# transmisorPCB_2_2.net
KiCad netlist of a schematic drawn in EAGLE
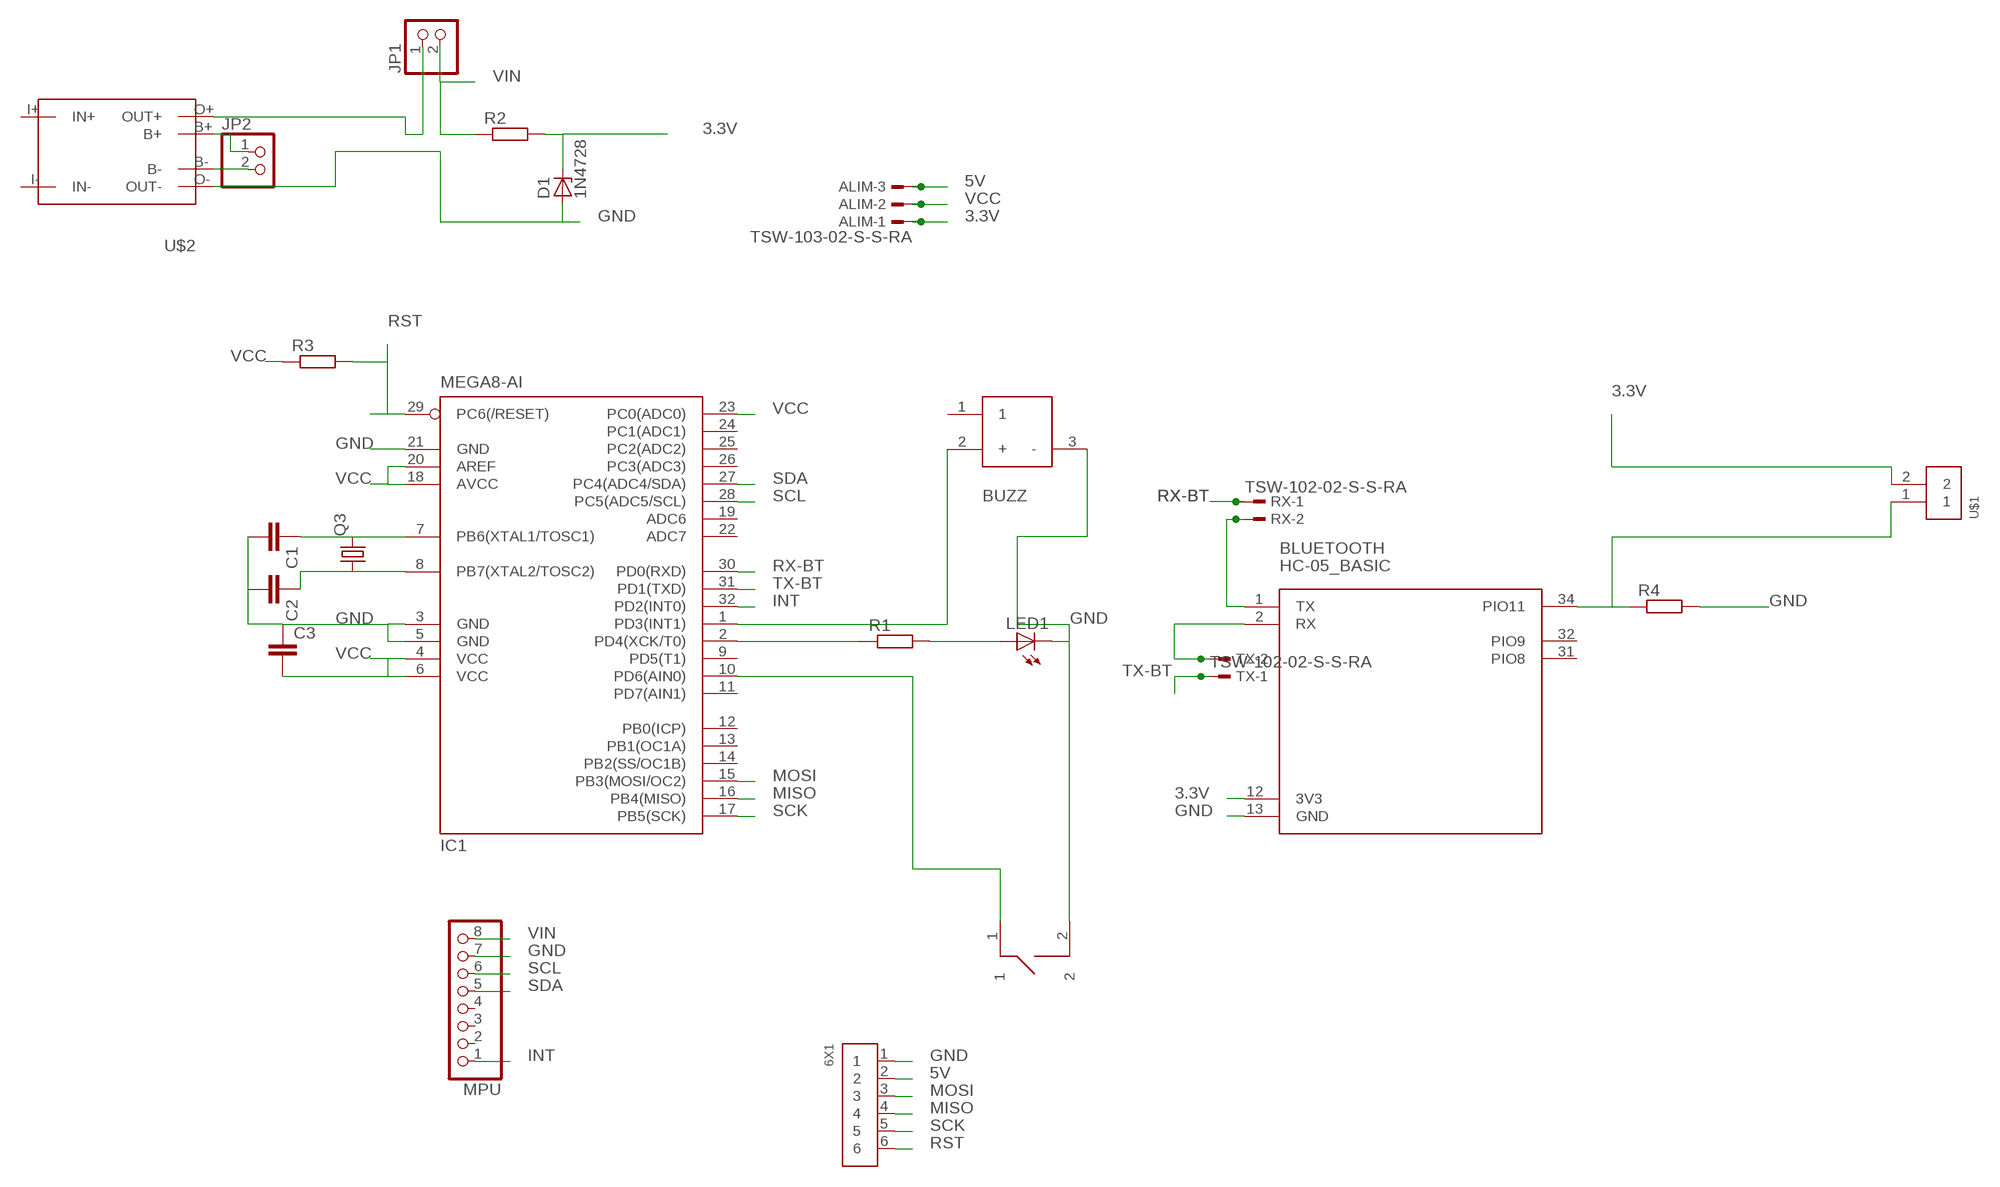
[diagram p0: schematic, sheet 1]

(export (version "E")
  (design (tool "Eeschema 10.0.6"))
  (components
    (comp (ref "6X1")
      (value "PINHEAD_1X6")
      (footprint "eagle-import:PINHEAD_125_1X6")
      (libsource (lib "eagle-import") (part "PINHEAD_1X6"))
    )
    (comp (ref "ALIM")
      (value "TSW-103-02-S-S-RA")
      (footprint "eagle-import:TSW-103-02-S-S-RA")
      (libsource (lib "eagle-import") (part "TSW-103-02-S-S-RA"))
    )
    (comp (ref "BLUETOOTH")
      (value "HC-05_BASIC")
      (footprint "eagle-import:BLUETOOTH_SMD")
      (libsource (lib "eagle-import") (part "HC-05_BASIC"))
    )
    (comp (ref "BUZZ")
      (value "SM05ET02A")
      (footprint "eagle-import:SM05ET02A")
      (libsource (lib "eagle-import") (part "SM05ET02A"))
    )
    (comp (ref "C1")
      (value "C-EUC0402K")
      (footprint "eagle-import:C0402K")
      (libsource (lib "eagle-import") (part "C-EUC0402K"))
    )
    (comp (ref "C2")
      (value "C-EUC0402K")
      (footprint "eagle-import:C0402K")
      (libsource (lib "eagle-import") (part "C-EUC0402K"))
    )
    (comp (ref "C3")
      (value "C-EUC0402K")
      (footprint "eagle-import:C0402K")
      (libsource (lib "eagle-import") (part "C-EUC0402K"))
    )
    (comp (ref "D1")
      (value "1N4728")
      (footprint "eagle-import:DO41Z10")
      (libsource (lib "eagle-import") (part "1N4728"))
    )
    (comp (ref "IC1")
      (value "MEGA8-AI")
      (footprint "eagle-import:TQFP32-08")
      (fields (field (name "MPN") "ATMEGA8-16AU"))
      (libsource (lib "eagle-import") (part "MEGA8-AI"))
    )
    (comp (ref "JP1")
      (value "PINHD-1X2")
      (footprint "eagle-import:1X02")
      (libsource (lib "eagle-import") (part "PINHD-1X2"))
    )
    (comp (ref "JP2")
      (value "PINHD-1X2")
      (footprint "eagle-import:1X02")
      (libsource (lib "eagle-import") (part "PINHD-1X2"))
    )
    (comp (ref "LED1")
      (value "LEDCHIPLED-0603-TTW")
      (footprint "eagle-import:CHIPLED-0603-TTW")
      (libsource (lib "eagle-import") (part "LEDCHIPLED-0603-TTW"))
    )
    (comp (ref "MPU")
      (value "PINHD-1X8")
      (footprint "eagle-import:1X08")
      (libsource (lib "eagle-import") (part "PINHD-1X8"))
    )
    (comp (ref "PUSH")
      (value "PUSH_SMD")
      (footprint "eagle-import:PUSH_SMD")
      (libsource (lib "eagle-import") (part "PUSH_SMD"))
    )
    (comp (ref "Q3")
      (value "CRYSTALHC49U70")
      (footprint "eagle-import:HC49U70")
      (libsource (lib "eagle-import") (part "CRYSTALHC49U70"))
    )
    (comp (ref "R1")
      (value "R-EU_M1206")
      (footprint "eagle-import:M1206")
      (libsource (lib "eagle-import") (part "R-EU_M1206"))
    )
    (comp (ref "R2")
      (value "R-EU_R2512")
      (footprint "eagle-import:R2512")
      (libsource (lib "eagle-import") (part "resistor_R-EU_R2512"))
    )
    (comp (ref "R3")
      (value "R-EU_M1206")
      (footprint "eagle-import:M1206")
      (libsource (lib "eagle-import") (part "R-EU_M1206"))
    )
    (comp (ref "R4")
      (value "R-EU_M1206")
      (footprint "eagle-import:M1206")
      (libsource (lib "eagle-import") (part "R-EU_M1206"))
    )
    (comp (ref "RX")
      (value "TSW-102-02-S-S-RA")
      (footprint "eagle-import:TSW-102-02-S-S-RA")
      (libsource (lib "eagle-import") (part "TSW-102-02-S-S-RA"))
    )
    (comp (ref "TX")
      (value "TSW-102-02-S-S-RA")
      (footprint "eagle-import:TSW-102-02-S-S-RA")
      (libsource (lib "eagle-import") (part "TSW-102-02-S-S-RA"))
    )
    (comp (ref "U$1")
      (value "CP150_1X2")
      (footprint "eagle-import:CP150_1X2")
      (libsource (lib "eagle-import") (part "CP150_1X2"))
    )
    (comp (ref "U$2")
      (value "TP4056")
      (footprint "eagle-import:TP4056")
      (libsource (lib "eagle-import") (part "TP4056"))
    )
  )
  (nets
    (net (code "1") (name "/3.3V") (class "Default")
      (node (ref "ALIM") (pin "1") (pinfunction "1_1") (pintype "passive"))
      (node (ref "BLUETOOTH") (pin "12") (pinfunction "3V3_12") (pintype "bidirectional"))
      (node (ref "D1") (pin "C") (pinfunction "C_C") (pintype "passive"))
      (node (ref "R2") (pin "2") (pinfunction "2_2") (pintype "passive"))
      (node (ref "U$1") (pin "2") (pinfunction "2_2") (pintype "bidirectional"))
    )
    (net (code "2") (name "/5V") (class "Default")
      (node (ref "6X1") (pin "2") (pinfunction "2_2") (pintype "bidirectional"))
      (node (ref "ALIM") (pin "3") (pinfunction "1_3") (pintype "passive"))
    )
    (net (code "3") (name "/GND") (class "Default")
      (node (ref "6X1") (pin "1") (pinfunction "1_1") (pintype "bidirectional"))
      (node (ref "BLUETOOTH") (pin "13") (pinfunction "GND_13") (pintype "bidirectional"))
      (node (ref "BUZZ") (pin "3") (pinfunction "-_3") (pintype "bidirectional"))
      (node (ref "C1") (pin "2") (pinfunction "2_2") (pintype "passive"))
      (node (ref "C2") (pin "2") (pinfunction "2_2") (pintype "passive"))
      (node (ref "C3") (pin "1") (pinfunction "1_1") (pintype "passive"))
      (node (ref "D1") (pin "A") (pinfunction "A_A") (pintype "passive"))
      (node (ref "IC1") (pin "21") (pinfunction "GND_21") (pintype "power_in"))
      (node (ref "IC1") (pin "3") (pinfunction "GND_3") (pintype "power_in"))
      (node (ref "IC1") (pin "5") (pinfunction "GND_5") (pintype "power_in"))
      (node (ref "LED1") (pin "C@1") (pinfunction "C_C@1") (pintype "passive"))
      (node (ref "MPU") (pin "7") (pinfunction "7_7") (pintype "passive"))
      (node (ref "PUSH") (pin "2") (pinfunction "2_2") (pintype "bidirectional"))
      (node (ref "R4") (pin "2") (pinfunction "2_2") (pintype "passive"))
      (node (ref "U$2") (pin "O-") (pinfunction "OUT-_O-") (pintype "bidirectional"))
    )
    (net (code "4") (name "/INT") (class "Default")
      (node (ref "IC1") (pin "32") (pinfunction "PD2(INT0)_32") (pintype "bidirectional"))
      (node (ref "MPU") (pin "1") (pinfunction "1_1") (pintype "passive"))
    )
    (net (code "5") (name "/MISO") (class "Default")
      (node (ref "6X1") (pin "4") (pinfunction "4_4") (pintype "bidirectional"))
      (node (ref "IC1") (pin "16") (pinfunction "PB4(MISO)_16") (pintype "bidirectional"))
    )
    (net (code "6") (name "/MOSI") (class "Default")
      (node (ref "6X1") (pin "3") (pinfunction "3_3") (pintype "bidirectional"))
      (node (ref "IC1") (pin "15") (pinfunction "PB3(MOSI/OC2)_15") (pintype "bidirectional"))
    )
    (net (code "7") (name "/RST") (class "Default")
      (node (ref "6X1") (pin "6") (pinfunction "6_6") (pintype "bidirectional"))
      (node (ref "IC1") (pin "29") (pinfunction "PC6(/RESET)_29") (pintype "bidirectional"))
      (node (ref "R3") (pin "2") (pinfunction "2_2") (pintype "passive"))
    )
    (net (code "8") (name "/RX-BT") (class "Default")
      (node (ref "IC1") (pin "30") (pinfunction "PD0(RXD)_30") (pintype "bidirectional"))
      (node (ref "RX") (pin "1") (pinfunction "1_1") (pintype "passive"))
    )
    (net (code "9") (name "/SCK") (class "Default")
      (node (ref "6X1") (pin "5") (pinfunction "5_5") (pintype "bidirectional"))
      (node (ref "IC1") (pin "17") (pinfunction "PB5(SCK)_17") (pintype "bidirectional"))
    )
    (net (code "10") (name "/SCL") (class "Default")
      (node (ref "IC1") (pin "28") (pinfunction "PC5(ADC5/SCL)_28") (pintype "bidirectional"))
      (node (ref "MPU") (pin "6") (pinfunction "6_6") (pintype "passive"))
    )
    (net (code "11") (name "/SDA") (class "Default")
      (node (ref "IC1") (pin "27") (pinfunction "PC4(ADC4/SDA)_27") (pintype "bidirectional"))
      (node (ref "MPU") (pin "5") (pinfunction "5_5") (pintype "passive"))
    )
    (net (code "12") (name "/TX-BT") (class "Default")
      (node (ref "IC1") (pin "31") (pinfunction "PD1(TXD)_31") (pintype "bidirectional"))
      (node (ref "TX") (pin "1") (pinfunction "1_1") (pintype "passive"))
    )
    (net (code "13") (name "/VCC") (class "Default")
      (node (ref "ALIM") (pin "2") (pinfunction "1_2") (pintype "passive"))
      (node (ref "C3") (pin "2") (pinfunction "2_2") (pintype "passive"))
      (node (ref "IC1") (pin "18") (pinfunction "AVCC_18") (pintype "power_in"))
      (node (ref "IC1") (pin "20") (pinfunction "AREF_20") (pintype "passive"))
      (node (ref "IC1") (pin "23") (pinfunction "PC0(ADC0)_23") (pintype "bidirectional"))
      (node (ref "IC1") (pin "4") (pinfunction "VCC_4") (pintype "power_in"))
      (node (ref "IC1") (pin "6") (pinfunction "VCC_6") (pintype "power_in"))
      (node (ref "R3") (pin "1") (pinfunction "1_1") (pintype "passive"))
    )
    (net (code "14") (name "/VIN") (class "Default")
      (node (ref "JP1") (pin "2") (pinfunction "2_2") (pintype "passive"))
      (node (ref "MPU") (pin "8") (pinfunction "8_8") (pintype "passive"))
      (node (ref "R2") (pin "1") (pinfunction "1_1") (pintype "passive"))
    )
    (net (code "15") (name "Net-(BLUETOOTH-PIO11)") (class "Default")
      (node (ref "BLUETOOTH") (pin "34") (pinfunction "PIO11_34") (pintype "bidirectional"))
      (node (ref "R4") (pin "1") (pinfunction "1_1") (pintype "passive"))
      (node (ref "U$1") (pin "1") (pinfunction "1_1") (pintype "bidirectional"))
    )
    (net (code "16") (name "Net-(BLUETOOTH-RX)") (class "Default")
      (node (ref "BLUETOOTH") (pin "2") (pinfunction "RX_2") (pintype "bidirectional"))
      (node (ref "TX") (pin "2") (pinfunction "1_2") (pintype "passive"))
    )
    (net (code "17") (name "Net-(BLUETOOTH-TX)") (class "Default")
      (node (ref "BLUETOOTH") (pin "1") (pinfunction "TX_1") (pintype "bidirectional"))
      (node (ref "RX") (pin "2") (pinfunction "1_2") (pintype "passive"))
    )
    (net (code "18") (name "Net-(BUZZ-+)") (class "Default")
      (node (ref "BUZZ") (pin "2") (pinfunction "+_2") (pintype "bidirectional"))
      (node (ref "IC1") (pin "1") (pinfunction "PD3(INT1)_1") (pintype "bidirectional"))
    )
    (net (code "19") (name "Net-(IC1-PB6(XTAL1{slash}TOSC1))") (class "Default")
      (node (ref "C1") (pin "1") (pinfunction "1_1") (pintype "passive"))
      (node (ref "IC1") (pin "7") (pinfunction "PB6(XTAL1/TOSC1)_7") (pintype "bidirectional"))
      (node (ref "Q3") (pin "2") (pinfunction "2_2") (pintype "passive"))
    )
    (net (code "20") (name "Net-(IC1-PB7(XTAL2{slash}TOSC2))") (class "Default")
      (node (ref "C2") (pin "1") (pinfunction "1_1") (pintype "passive"))
      (node (ref "IC1") (pin "8") (pinfunction "PB7(XTAL2/TOSC2)_8") (pintype "bidirectional"))
      (node (ref "Q3") (pin "1") (pinfunction "1_1") (pintype "passive"))
    )
    (net (code "21") (name "Net-(IC1-PD4(XCK{slash}T0))") (class "Default")
      (node (ref "IC1") (pin "2") (pinfunction "PD4(XCK/T0)_2") (pintype "bidirectional"))
      (node (ref "R1") (pin "1") (pinfunction "1_1") (pintype "passive"))
    )
    (net (code "22") (name "Net-(IC1-PD6(AIN0))") (class "Default")
      (node (ref "IC1") (pin "10") (pinfunction "PD6(AIN0)_10") (pintype "bidirectional"))
      (node (ref "PUSH") (pin "1") (pinfunction "1_1") (pintype "bidirectional"))
    )
    (net (code "23") (name "Net-(JP2-Pad1)") (class "Default")
      (node (ref "JP2") (pin "1") (pinfunction "1_1") (pintype "passive"))
      (node (ref "U$2") (pin "B+") (pinfunction "B+_B+") (pintype "bidirectional"))
    )
    (net (code "24") (name "Net-(JP2-Pad2)") (class "Default")
      (node (ref "JP2") (pin "2") (pinfunction "2_2") (pintype "passive"))
      (node (ref "U$2") (pin "B-") (pinfunction "B-_B-") (pintype "bidirectional"))
    )
    (net (code "25") (name "Net-(LED1-A)") (class "Default")
      (node (ref "LED1") (pin "A@1") (pinfunction "A_A@1") (pintype "passive"))
      (node (ref "R1") (pin "2") (pinfunction "2_2") (pintype "passive"))
    )
    (net (code "26") (name "Net-(U$2-OUT+)") (class "Default")
      (node (ref "JP1") (pin "1") (pinfunction "1_1") (pintype "passive"))
      (node (ref "U$2") (pin "O+") (pinfunction "OUT+_O+") (pintype "bidirectional"))
    )
    (net (code "27") (name "unconnected-(BLUETOOTH-PIO8-Pad31)") (class "Default")
      (node (ref "BLUETOOTH") (pin "31") (pinfunction "PIO8_31") (pintype "bidirectional"))
    )
    (net (code "28") (name "unconnected-(BLUETOOTH-PIO9-Pad32)") (class "Default")
      (node (ref "BLUETOOTH") (pin "32") (pinfunction "PIO9_32") (pintype "bidirectional"))
    )
    (net (code "29") (name "unconnected-(BUZZ-Pad1)") (class "Default")
      (node (ref "BUZZ") (pin "1") (pinfunction "1_1") (pintype "bidirectional"))
    )
    (net (code "30") (name "unconnected-(IC1-ADC6-Pad19)") (class "Default")
      (node (ref "IC1") (pin "19") (pinfunction "ADC6_19") (pintype "bidirectional"))
    )
    (net (code "31") (name "unconnected-(IC1-ADC7-Pad22)") (class "Default")
      (node (ref "IC1") (pin "22") (pinfunction "ADC7_22") (pintype "bidirectional"))
    )
    (net (code "32") (name "unconnected-(IC1-PB0(ICP)-Pad12)") (class "Default")
      (node (ref "IC1") (pin "12") (pinfunction "PB0(ICP)_12") (pintype "bidirectional"))
    )
    (net (code "33") (name "unconnected-(IC1-PB1(OC1A)-Pad13)") (class "Default")
      (node (ref "IC1") (pin "13") (pinfunction "PB1(OC1A)_13") (pintype "bidirectional"))
    )
    (net (code "34") (name "unconnected-(IC1-PB2(SS{slash}OC1B)-Pad14)") (class "Default")
      (node (ref "IC1") (pin "14") (pinfunction "PB2(SS/OC1B)_14") (pintype "bidirectional"))
    )
    (net (code "35") (name "unconnected-(IC1-PC1(ADC1)-Pad24)") (class "Default")
      (node (ref "IC1") (pin "24") (pinfunction "PC1(ADC1)_24") (pintype "bidirectional"))
    )
    (net (code "36") (name "unconnected-(IC1-PC2(ADC2)-Pad25)") (class "Default")
      (node (ref "IC1") (pin "25") (pinfunction "PC2(ADC2)_25") (pintype "bidirectional"))
    )
    (net (code "37") (name "unconnected-(IC1-PC3(ADC3)-Pad26)") (class "Default")
      (node (ref "IC1") (pin "26") (pinfunction "PC3(ADC3)_26") (pintype "bidirectional"))
    )
    (net (code "38") (name "unconnected-(IC1-PD5(T1)-Pad9)") (class "Default")
      (node (ref "IC1") (pin "9") (pinfunction "PD5(T1)_9") (pintype "bidirectional"))
    )
    (net (code "39") (name "unconnected-(IC1-PD7(AIN1)-Pad11)") (class "Default")
      (node (ref "IC1") (pin "11") (pinfunction "PD7(AIN1)_11") (pintype "bidirectional"))
    )
    (net (code "40") (name "unconnected-(MPU-Pad2)") (class "Default")
      (node (ref "MPU") (pin "2") (pinfunction "2_2") (pintype "passive"))
    )
    (net (code "41") (name "unconnected-(MPU-Pad3)") (class "Default")
      (node (ref "MPU") (pin "3") (pinfunction "3_3") (pintype "passive"))
    )
    (net (code "42") (name "unconnected-(MPU-Pad4)") (class "Default")
      (node (ref "MPU") (pin "4") (pinfunction "4_4") (pintype "passive"))
    )
    (net (code "43") (name "unconnected-(U$2-IN+-PadI+)") (class "Default")
      (node (ref "U$2") (pin "I+") (pinfunction "IN+_I+") (pintype "bidirectional"))
    )
    (net (code "44") (name "unconnected-(U$2-IN--PadI-)") (class "Default")
      (node (ref "U$2") (pin "I-") (pinfunction "IN-_I-") (pintype "bidirectional"))
    )
  )
)
